# 3_-STM32F103_Debugger.net
KiCad netlist of a schematic drawn in Altium Designer
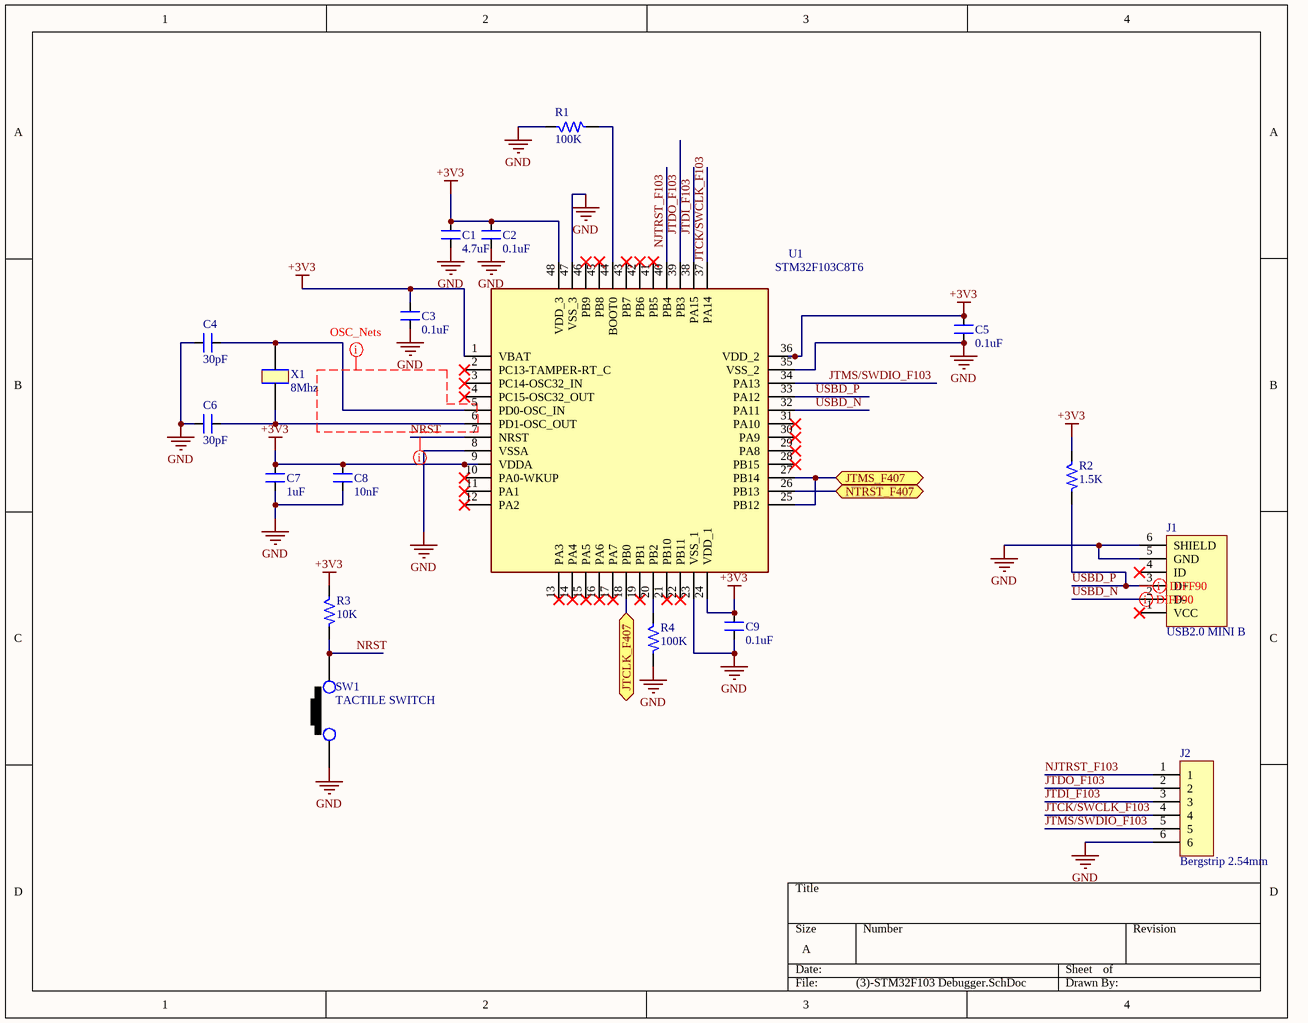
[diagram p0: (3)-STM32F103 Debugger.SchDoc]

(export (version "E")
  (design (tool "Eeschema 10.0.6"))
  (components
    (comp (ref "C1")
      (value "4.7uF")
      (footprint "CAP_0805")
      (description "4.7µF ±10% 50V Ceramic Capacitor X5R 0805 (2012 Metric)")
      (fields
        (field (name "MANUFACTURER") "Yageo")
        (field (name "MANUFACTURER PART NUMBER") "GRM21BR61H475KE51L")
      )
      (libsource (lib "ESTEEMPCBLIB") (part "CAP_4.7uF-50V-10%-0805"))
    )
    (comp (ref "C2")
      (value "0.1uF")
      (footprint "CAP_0805")
      (description "0.1µF ±10% 50V Ceramic Capacitor X7R 0805 (2012 Metric)")
      (fields
        (field (name "MANUFACTURER") "Samsung")
        (field (name "MANUFACTURER PART NUMBER") "CL21B104KBCNNNC")
      )
      (libsource (lib "ESTEEMPCBLIB") (part "CAP_0.1uF-50V-10%-0805"))
    )
    (comp (ref "C3")
      (value "0.1uF")
      (footprint "CAP_0805")
      (description "0.1µF ±10% 50V Ceramic Capacitor X7R 0805 (2012 Metric)")
      (fields
        (field (name "MANUFACTURER") "Samsung")
        (field (name "MANUFACTURER PART NUMBER") "CL21B104KBCNNNC")
      )
      (libsource (lib "ESTEEMPCBLIB") (part "CAP_0.1uF-50V-10%-0805"))
    )
    (comp (ref "C4")
      (value "30pF")
      (footprint "CAP_0805")
      (description "±10% 50V Ceramic Capacitor C0G, NP0 0805 (2012 Metric)")
      (fields
        (field (name "MANUFACTURER PART NUMBER") "C0805C300K5GAC7800")
        (field (name "MANUFACTURER") "KEMET")
      )
      (libsource (lib "ESTEEMPCBLIB") (part "CAP_30pF-50V-10%-0805"))
    )
    (comp (ref "C5")
      (value "0.1uF")
      (footprint "CAP_0805")
      (description "0.1µF ±10% 50V Ceramic Capacitor X7R 0805 (2012 Metric)")
      (fields
        (field (name "MANUFACTURER") "Samsung")
        (field (name "MANUFACTURER PART NUMBER") "CL21B104KBCNNNC")
      )
      (libsource (lib "ESTEEMPCBLIB") (part "CAP_0.1uF-50V-10%-0805"))
    )
    (comp (ref "C6")
      (value "30pF")
      (footprint "CAP_0805")
      (description "±10% 50V Ceramic Capacitor C0G, NP0 0805 (2012 Metric)")
      (fields
        (field (name "MANUFACTURER PART NUMBER") "C0805C300K5GAC7800")
        (field (name "MANUFACTURER") "KEMET")
      )
      (libsource (lib "ESTEEMPCBLIB") (part "CAP_30pF-50V-10%-0805"))
    )
    (comp (ref "C7")
      (value "1uF")
      (footprint "CAP_0805")
      (description "1µF ±5% 50V Ceramic Capacitor X7R 0805 (2012 Metric)")
      (fields
        (field (name "MANUFACTURER") "Samsung")
        (field (name "MANUFACTURER PART NUMBER") "CC0805JKX7R9BB105")
      )
      (libsource (lib "ESTEEMPCBLIB") (part "CAP_1uF-50V-5%-0805"))
    )
    (comp (ref "C8")
      (value "10nF")
      (footprint "CAP_0805")
      (description "10000pF ±10% 50V Ceramic Capacitor X7R 0805 (2012 Metric)")
      (fields
        (field (name "MANUFACTURER") "Samsung")
        (field (name "MANUFACTURER PART NUMBER") "C0805C103K5RECAUTO")
      )
      (libsource (lib "ESTEEMPCBLIB") (part "CAP_10nF-50V-10%-0805"))
    )
    (comp (ref "C9")
      (value "0.1uF")
      (footprint "CAP_0805")
      (description "0.1µF ±10% 50V Ceramic Capacitor X7R 0805 (2012 Metric)")
      (fields
        (field (name "MANUFACTURER") "Samsung")
        (field (name "MANUFACTURER PART NUMBER") "CL21B104KBCNNNC")
      )
      (libsource (lib "ESTEEMPCBLIB") (part "CAP_0.1uF-50V-10%-0805"))
    )
    (comp (ref "J1")
      (value "USB2.0 MINI B")
      (footprint "CON_690-005-299-043")
      (description "USB - mini B USB 2.0 Receptacle Connector 5 Position Surface Mount, Right Angle")
      (fields
        (field (name "MANUFACTURER") "EDAC")
        (field (name "MANUFACTURER PART NUMBER") "690-005-299-043")
      )
      (libsource (lib "ESTEEMPCBLIB") (part "CON_USB2.0-MINIB-SMD"))
    )
    (comp (ref "J2")
      (value "Bergstrip 2.54mm")
      (footprint "CON6_100_59D78_TH_ST")
      (description "6 Pins, 1 Row 2.54mm Pitch, Straight bergstrip, Female")
      (fields (field (name "MANUFACTURER") "Molex") (field (name "MANUFACTURER PART NUMBER") "22-10-2061"))
      (libsource (lib "ESTEEMPCBLIB") (part "CON-BS-SKT_6X1-100-ST-TH"))
    )
    (comp (ref "R1")
      (value "100K")
      (footprint "RES_0603")
      (description "100 kOhms ±1% 0.1W, 1/10W Chip Resistor 0603 (1608 Metric) Automotive AEC-Q200 Thick Film")
      (fields
        (field (name "MANUFACTURER") "Stackpole Electronics")
        (field (name "MANUFACTURER PART NUMBER") "RMCF0603FT100K")
      )
      (libsource (lib "ESTEEMPCBLIB") (part "RES_100K-0.1W-1%-0603"))
    )
    (comp (ref "R2")
      (value "1.5K")
      (footprint "RES_0805")
      (description "1.5 kOhms ±1% 0.125W, 1/8W Chip Resistor 0805 (2012 Metric) Thick Film")
      (fields
        (field (name "MANUFACTURER") "TE Connectivity Passive Product")
        (field (name "MANUFACTURER PART NUMBER") "CRG0805F1K5")
      )
      (libsource (lib "ESTEEMPCBLIB") (part "RES_1.5K-0.125W-1%-0805"))
    )
    (comp (ref "R3")
      (value "10K")
      (footprint "RES_0603")
      (description "10 kOhms ±1% 0.1W, 1/10W Chip Resistor 0603 (1608 Metric) Automotive AEC-Q200 Thick Film")
      (fields (field (name "MANUFACTURER") "Walsin") (field (name "MANUFACTURER PART NUMBER") "WR06X1002FTL"))
      (libsource (lib "ESTEEMPCBLIB") (part "RES_10K-0.1W-1%-0603"))
    )
    (comp (ref "R4")
      (value "100K")
      (footprint "RES_0603")
      (description "100 kOhms ±1% 0.1W, 1/10W Chip Resistor 0603 (1608 Metric) Automotive AEC-Q200 Thick Film")
      (fields
        (field (name "MANUFACTURER") "Stackpole Electronics")
        (field (name "MANUFACTURER PART NUMBER") "RMCF0603FT100K")
      )
      (libsource (lib "ESTEEMPCBLIB") (part "RES_100K-0.1W-1%-0603"))
    )
    (comp (ref "SW1")
      (value "TACTILE SWITCH")
      (footprint "SW_342_SMD")
      (description "Tactile Switch SPST-NO Top Actuated Surface Mount")
      (fields
        (field (name "MANUFACTURER") "ITT C&K")
        (field (name "MANUFACTURER PART NUMBER") "RS-282G05A3-SMRT")
      )
      (libsource (lib "ESTEEMPCBLIB") (part "SW1_RS-282G05A3-SMRT-SMD"))
    )
    (comp (ref "U1")
      (value "STM32F103C8T6")
      (footprint "LQFP-48_19.6_393_58X11_SMD")
      (description "ARM® Cortex®-M3 STM32F1 Microcontroller IC 32-Bit 72MHz 64KB (64K x 8) FLASH 48-LQFP (7x7)")
      (fields (field (name "MANUFACTURER") "STMicroelectronics"))
      (libsource (lib "ESTEEMPCBLIB") (part "IC_STM32F103C8T6"))
    )
    (comp (ref "X1")
      (value "8Mhz")
      (footprint "XTAL_314_240X47_SMD")
      (description "8MHz ±30ppm Crystal 32pF 60 Ohms HC-49/US")
      (fields
        (field (name "MANUFACTURER") "Fox Electronics")
        (field (name "MANUFACTURER PART NUMBER") "ECS-80-32-5PX-TR")
      )
      (libsource (lib "ESTEEMPCBLIB") (part "XTAL_8MHZ-ECS-80-32-5PX-SMD"))
    )
  )
  (nets
    (net (code "1") (name "+3V3") (class "Default")
      (node (ref "C1") (pin "1") (pinfunction "1_1") (pintype "passive"))
      (node (ref "C2") (pin "1") (pinfunction "1_1") (pintype "passive"))
      (node (ref "C3") (pin "1") (pinfunction "1_1") (pintype "passive"))
      (node (ref "C5") (pin "1") (pinfunction "1_1") (pintype "passive"))
      (node (ref "C7") (pin "1") (pinfunction "1_1") (pintype "passive"))
      (node (ref "C8") (pin "1") (pinfunction "1_1") (pintype "passive"))
      (node (ref "C9") (pin "1") (pinfunction "1_1") (pintype "passive"))
      (node (ref "R2") (pin "1") (pinfunction "1_1") (pintype "passive"))
      (node (ref "R3") (pin "1") (pinfunction "1_1") (pintype "passive"))
      (node (ref "U1") (pin "1") (pinfunction "VBAT_1") (pintype "passive"))
      (node (ref "U1") (pin "24") (pinfunction "VDD_1_24") (pintype "passive"))
      (node (ref "U1") (pin "36") (pinfunction "VDD_2_36") (pintype "passive"))
      (node (ref "U1") (pin "48") (pinfunction "VDD_3_48") (pintype "passive"))
      (node (ref "U1") (pin "9") (pinfunction "VDDA_9") (pintype "passive"))
    )
    (net (code "2") (name "/JTCK{slash}SWCLK_F103") (class "Default")
      (node (ref "J2") (pin "4") (pinfunction "4_4") (pintype "passive"))
      (node (ref "U1") (pin "37") (pinfunction "PA14_37") (pintype "passive"))
    )
    (net (code "3") (name "/JTCLK_F407") (class "Default")
      (node (ref "U1") (pin "18") (pinfunction "PB0_18") (pintype "passive"))
    )
    (net (code "4") (name "/JTDI_F103") (class "Default")
      (node (ref "J2") (pin "3") (pinfunction "3_3") (pintype "passive"))
      (node (ref "U1") (pin "38") (pinfunction "PA15_38") (pintype "passive"))
    )
    (net (code "5") (name "/JTDO_F103") (class "Default")
      (node (ref "J2") (pin "2") (pinfunction "2_2") (pintype "passive"))
      (node (ref "U1") (pin "39") (pinfunction "PB3_39") (pintype "passive"))
    )
    (net (code "6") (name "/JTMS_F407") (class "Default")
      (node (ref "U1") (pin "25") (pinfunction "PB12_25") (pintype "passive"))
      (node (ref "U1") (pin "27") (pinfunction "PB14_27") (pintype "passive"))
    )
    (net (code "7") (name "/JTMS{slash}SWDIO_F103") (class "Default")
      (node (ref "J2") (pin "5") (pinfunction "5_5") (pintype "passive"))
      (node (ref "U1") (pin "34") (pinfunction "PA13_34") (pintype "passive"))
    )
    (net (code "8") (name "/NJTRST_F103") (class "Default")
      (node (ref "J2") (pin "1") (pinfunction "1_1") (pintype "passive"))
      (node (ref "U1") (pin "40") (pinfunction "PB4_40") (pintype "passive"))
    )
    (net (code "9") (name "/NRST") (class "Default")
      (node (ref "R3") (pin "2") (pinfunction "2_2") (pintype "passive"))
      (node (ref "SW1") (pin "2") (pinfunction "2_2") (pintype "passive"))
      (node (ref "U1") (pin "7") (pinfunction "NRST_7") (pintype "passive"))
    )
    (net (code "10") (name "/NTRST_F407") (class "Default")
      (node (ref "U1") (pin "26") (pinfunction "PB13_26") (pintype "passive"))
    )
    (net (code "11") (name "/USBD_N") (class "Default")
      (node (ref "J1") (pin "2") (pinfunction "D-_2") (pintype "passive"))
      (node (ref "U1") (pin "32") (pinfunction "PA11_32") (pintype "passive"))
    )
    (net (code "12") (name "/USBD_P") (class "Default")
      (node (ref "J1") (pin "3") (pinfunction "D+_3") (pintype "passive"))
      (node (ref "R2") (pin "2") (pinfunction "2_2") (pintype "passive"))
      (node (ref "U1") (pin "33") (pinfunction "PA12_33") (pintype "passive"))
    )
    (net (code "13") (name "GND") (class "Default")
      (node (ref "C1") (pin "2") (pinfunction "2_2") (pintype "passive"))
      (node (ref "C2") (pin "2") (pinfunction "2_2") (pintype "passive"))
      (node (ref "C3") (pin "2") (pinfunction "2_2") (pintype "passive"))
      (node (ref "C4") (pin "1") (pinfunction "1_1") (pintype "passive"))
      (node (ref "C5") (pin "2") (pinfunction "2_2") (pintype "passive"))
      (node (ref "C6") (pin "1") (pinfunction "1_1") (pintype "passive"))
      (node (ref "C7") (pin "2") (pinfunction "2_2") (pintype "passive"))
      (node (ref "C8") (pin "2") (pinfunction "2_2") (pintype "passive"))
      (node (ref "C9") (pin "2") (pinfunction "2_2") (pintype "passive"))
      (node (ref "J1") (pin "5") (pinfunction "GND_5") (pintype "passive"))
      (node (ref "J1") (pin "6") (pinfunction "SHIELD_6") (pintype "passive"))
      (node (ref "J2") (pin "6") (pinfunction "6_6") (pintype "passive"))
      (node (ref "R1") (pin "1") (pinfunction "1_1") (pintype "passive"))
      (node (ref "R4") (pin "2") (pinfunction "2_2") (pintype "passive"))
      (node (ref "SW1") (pin "1") (pinfunction "1_1") (pintype "passive"))
      (node (ref "U1") (pin "23") (pinfunction "VSS_1_23") (pintype "passive"))
      (node (ref "U1") (pin "35") (pinfunction "VSS_2_35") (pintype "passive"))
      (node (ref "U1") (pin "47") (pinfunction "VSS_3_47") (pintype "passive"))
      (node (ref "U1") (pin "8") (pinfunction "VSSA_8") (pintype "passive"))
    )
    (net (code "14") (name "Net-(U1-BOOT0)") (class "Default")
      (node (ref "R1") (pin "2") (pinfunction "2_2") (pintype "passive"))
      (node (ref "U1") (pin "44") (pinfunction "BOOT0_44") (pintype "passive"))
    )
    (net (code "15") (name "Net-(U1-PB2)") (class "Default")
      (node (ref "R4") (pin "1") (pinfunction "1_1") (pintype "passive"))
      (node (ref "U1") (pin "20") (pinfunction "PB2_20") (pintype "passive"))
    )
    (net (code "16") (name "Net-(U1-PD0-OSC_IN)") (class "Default")
      (node (ref "C4") (pin "2") (pinfunction "2_2") (pintype "passive"))
      (node (ref "U1") (pin "5") (pinfunction "PD0-OSC_IN_5") (pintype "passive"))
      (node (ref "X1") (pin "1") (pinfunction "1_1") (pintype "passive"))
    )
    (net (code "17") (name "Net-(U1-PD1-OSC_OUT)") (class "Default")
      (node (ref "C6") (pin "2") (pinfunction "2_2") (pintype "passive"))
      (node (ref "U1") (pin "6") (pinfunction "PD1-OSC_OUT_6") (pintype "passive"))
      (node (ref "X1") (pin "2") (pinfunction "2_2") (pintype "passive"))
    )
    (net (code "18") (name "unconnected-(J1-ID-Pad4)") (class "Default")
      (node (ref "J1") (pin "4") (pinfunction "ID_4") (pintype "passive+no_connect"))
    )
    (net (code "19") (name "unconnected-(J1-VCC-Pad1)") (class "Default")
      (node (ref "J1") (pin "1") (pinfunction "VCC_1") (pintype "passive+no_connect"))
    )
    (net (code "20") (name "unconnected-(U1-PA0-WKUP-Pad10)") (class "Default")
      (node (ref "U1") (pin "10") (pinfunction "PA0-WKUP_10") (pintype "passive+no_connect"))
    )
    (net (code "21") (name "unconnected-(U1-PA1-Pad11)") (class "Default")
      (node (ref "U1") (pin "11") (pinfunction "PA1_11") (pintype "passive+no_connect"))
    )
    (net (code "22") (name "unconnected-(U1-PA2-Pad12)") (class "Default")
      (node (ref "U1") (pin "12") (pinfunction "PA2_12") (pintype "passive+no_connect"))
    )
    (net (code "23") (name "unconnected-(U1-PA3-Pad13)") (class "Default")
      (node (ref "U1") (pin "13") (pinfunction "PA3_13") (pintype "passive+no_connect"))
    )
    (net (code "24") (name "unconnected-(U1-PA4-Pad14)") (class "Default")
      (node (ref "U1") (pin "14") (pinfunction "PA4_14") (pintype "passive+no_connect"))
    )
    (net (code "25") (name "unconnected-(U1-PA5-Pad15)") (class "Default")
      (node (ref "U1") (pin "15") (pinfunction "PA5_15") (pintype "passive+no_connect"))
    )
    (net (code "26") (name "unconnected-(U1-PA6-Pad16)") (class "Default")
      (node (ref "U1") (pin "16") (pinfunction "PA6_16") (pintype "passive+no_connect"))
    )
    (net (code "27") (name "unconnected-(U1-PA7-Pad17)") (class "Default")
      (node (ref "U1") (pin "17") (pinfunction "PA7_17") (pintype "passive+no_connect"))
    )
    (net (code "28") (name "unconnected-(U1-PA8-Pad29)") (class "Default")
      (node (ref "U1") (pin "29") (pinfunction "PA8_29") (pintype "passive+no_connect"))
    )
    (net (code "29") (name "unconnected-(U1-PA9-Pad30)") (class "Default")
      (node (ref "U1") (pin "30") (pinfunction "PA9_30") (pintype "passive+no_connect"))
    )
    (net (code "30") (name "unconnected-(U1-PA10-Pad31)") (class "Default")
      (node (ref "U1") (pin "31") (pinfunction "PA10_31") (pintype "passive+no_connect"))
    )
    (net (code "31") (name "unconnected-(U1-PB1-Pad19)") (class "Default")
      (node (ref "U1") (pin "19") (pinfunction "PB1_19") (pintype "passive+no_connect"))
    )
    (net (code "32") (name "unconnected-(U1-PB5-Pad41)") (class "Default")
      (node (ref "U1") (pin "41") (pinfunction "PB5_41") (pintype "passive+no_connect"))
    )
    (net (code "33") (name "unconnected-(U1-PB6-Pad42)") (class "Default")
      (node (ref "U1") (pin "42") (pinfunction "PB6_42") (pintype "passive+no_connect"))
    )
    (net (code "34") (name "unconnected-(U1-PB7-Pad43)") (class "Default")
      (node (ref "U1") (pin "43") (pinfunction "PB7_43") (pintype "passive+no_connect"))
    )
    (net (code "35") (name "unconnected-(U1-PB8-Pad45)") (class "Default")
      (node (ref "U1") (pin "45") (pinfunction "PB8_45") (pintype "passive+no_connect"))
    )
    (net (code "36") (name "unconnected-(U1-PB9-Pad46)") (class "Default")
      (node (ref "U1") (pin "46") (pinfunction "PB9_46") (pintype "passive+no_connect"))
    )
    (net (code "37") (name "unconnected-(U1-PB10-Pad21)") (class "Default")
      (node (ref "U1") (pin "21") (pinfunction "PB10_21") (pintype "passive+no_connect"))
    )
    (net (code "38") (name "unconnected-(U1-PB11-Pad22)") (class "Default")
      (node (ref "U1") (pin "22") (pinfunction "PB11_22") (pintype "passive+no_connect"))
    )
    (net (code "39") (name "unconnected-(U1-PB15-Pad28)") (class "Default")
      (node (ref "U1") (pin "28") (pinfunction "PB15_28") (pintype "passive+no_connect"))
    )
    (net (code "40") (name "unconnected-(U1-PC13-TAMPER-RT_C-Pad2)") (class "Default")
      (node (ref "U1") (pin "2") (pinfunction "PC13-TAMPER-RT_C_2") (pintype "passive+no_connect"))
    )
    (net (code "41") (name "unconnected-(U1-PC14-OSC32_IN-Pad3)") (class "Default")
      (node (ref "U1") (pin "3") (pinfunction "PC14-OSC32_IN_3") (pintype "passive+no_connect"))
    )
    (net (code "42") (name "unconnected-(U1-PC15-OSC32_OUT-Pad4)") (class "Default")
      (node (ref "U1") (pin "4") (pinfunction "PC15-OSC32_OUT_4") (pintype "passive+no_connect"))
    )
  )
)
